# Oscillator.net
KiCad netlist of a schematic drawn in Altium Designer
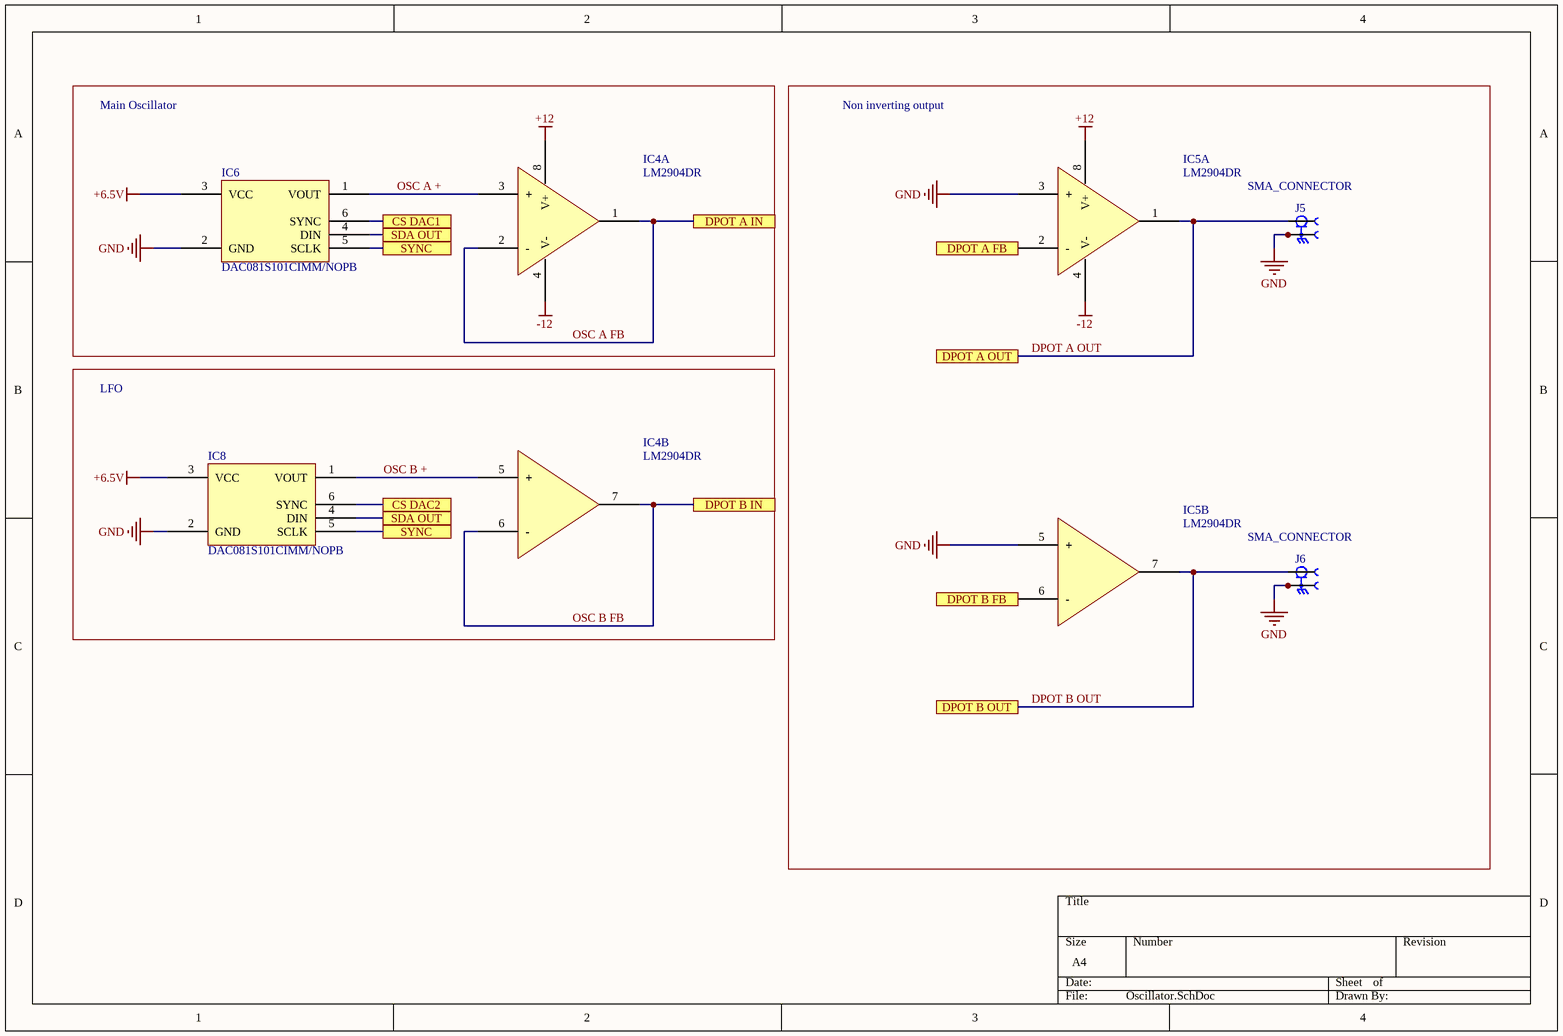
[diagram p0: Oscillator.SchDoc]

(export (version "E")
  (design (tool "Eeschema 10.0.6"))
  (components
    (comp (ref "IC4")
      (value "LM2904DR")
      (footprint "TI SOIC-8 D")
      (description "IC OPAMP GP 2 CIRCUIT 8SOIC")
      (fields (field (name "MANUFACTURER") "Texas Instruments"))
      (libsource (lib "Celestial Altium Library - altium_library(1)") (part "TI LM2904DR"))
    )
    (comp (ref "IC5")
      (value "LM2904DR")
      (footprint "TI SOIC-8 D")
      (description "IC OPAMP GP 2 CIRCUIT 8SOIC")
      (fields (field (name "MANUFACTURER") "Texas Instruments"))
      (libsource (lib "Celestial Altium Library - altium_library(1)") (part "TI LM2904DR"))
    )
    (comp (ref "IC6")
      (value "DAC081S101CIMM/NOPB")
      (footprint "TI VSSOP-8 DGK")
      (description "IC DAC 8BIT V-OUT 8VSSOP")
      (libsource (lib "Celestial Altium Library - altium_library(1)") (part "TI DAC081S101CIMM"))
    )
    (comp (ref "IC8")
      (value "DAC081S101CIMM/NOPB")
      (footprint "TI VSSOP-8 DGK")
      (description "IC DAC 8BIT V-OUT 8VSSOP")
      (libsource (lib "Celestial Altium Library - altium_library(1)") (part "TI DAC081S101CIMM"))
    )
    (comp (ref "J5")
      (value "SMA_CONNECTOR")
      (footprint "LPRS_SMA_CONNECTOR")
      (description "Straight SMA Connector")
      (fields (field (name "MP") "altium_native_batch"))
      (libsource (lib "SMA_CONNECTOR") (part "SMA_CONNECTOR"))
    )
    (comp (ref "J6")
      (value "SMA_CONNECTOR")
      (footprint "LPRS_SMA_CONNECTOR")
      (description "Straight SMA Connector")
      (fields (field (name "MP") "altium_native_batch"))
      (libsource (lib "SMA_CONNECTOR") (part "SMA_CONNECTOR"))
    )
  )
  (nets
    (net (code "1") (name "+6.5V") (class "Default")
      (node (ref "IC6") (pin "3") (pinfunction "VCC_3") (pintype "passive"))
      (node (ref "IC8") (pin "3") (pinfunction "VCC_3") (pintype "passive"))
    )
    (net (code "2") (name "+12") (class "Default")
      (node (ref "IC4") (pin "8") (pinfunction "V+_8") (pintype "passive"))
      (node (ref "IC5") (pin "8") (pinfunction "V+_8") (pintype "passive"))
    )
    (net (code "3") (name "-12") (class "Default")
      (node (ref "IC4") (pin "4") (pinfunction "V-_4") (pintype "passive"))
      (node (ref "IC5") (pin "4") (pinfunction "V-_4") (pintype "passive"))
    )
    (net (code "4") (name "/CS DAC1") (class "Default")
      (node (ref "IC6") (pin "6") (pinfunction "SYNC_6") (pintype "passive"))
    )
    (net (code "5") (name "/CS DAC2") (class "Default")
      (node (ref "IC8") (pin "6") (pinfunction "SYNC_6") (pintype "passive"))
    )
    (net (code "6") (name "/DPOT A FB") (class "Default")
      (node (ref "IC5") (pin "2") (pinfunction "-_2") (pintype "passive"))
    )
    (net (code "7") (name "/DPOT A OUT") (class "Default")
      (node (ref "IC5") (pin "1") (pinfunction "OUTA_1") (pintype "passive"))
      (node (ref "J5") (pin "1") (pinfunction "1_1") (pintype "passive"))
    )
    (net (code "8") (name "/DPOT B FB") (class "Default")
      (node (ref "IC5") (pin "6") (pinfunction "-_6") (pintype "passive"))
    )
    (net (code "9") (name "/DPOT B OUT") (class "Default")
      (node (ref "IC5") (pin "7") (pinfunction "OUTB_7") (pintype "passive"))
      (node (ref "J6") (pin "1") (pinfunction "1_1") (pintype "passive"))
    )
    (net (code "10") (name "/OSC A +") (class "Default")
      (node (ref "IC4") (pin "3") (pinfunction "+_3") (pintype "passive"))
      (node (ref "IC6") (pin "1") (pinfunction "VOUT_1") (pintype "passive"))
    )
    (net (code "11") (name "/OSC A FB") (class "Default")
      (node (ref "IC4") (pin "1") (pinfunction "OUTA_1") (pintype "passive"))
      (node (ref "IC4") (pin "2") (pinfunction "-_2") (pintype "passive"))
    )
    (net (code "12") (name "/OSC B +") (class "Default")
      (node (ref "IC4") (pin "5") (pinfunction "+_5") (pintype "passive"))
      (node (ref "IC8") (pin "1") (pinfunction "VOUT_1") (pintype "passive"))
    )
    (net (code "13") (name "/OSC B FB") (class "Default")
      (node (ref "IC4") (pin "6") (pinfunction "-_6") (pintype "passive"))
      (node (ref "IC4") (pin "7") (pinfunction "OUTB_7") (pintype "passive"))
    )
    (net (code "14") (name "/SDA OUT") (class "Default")
      (node (ref "IC6") (pin "4") (pinfunction "DIN_4") (pintype "passive"))
      (node (ref "IC8") (pin "4") (pinfunction "DIN_4") (pintype "passive"))
    )
    (net (code "15") (name "/SYNC") (class "Default")
      (node (ref "IC6") (pin "5") (pinfunction "SCLK_5") (pintype "passive"))
      (node (ref "IC8") (pin "5") (pinfunction "SCLK_5") (pintype "passive"))
    )
    (net (code "16") (name "GND") (class "Default")
      (node (ref "IC5") (pin "3") (pinfunction "+_3") (pintype "passive"))
      (node (ref "IC5") (pin "5") (pinfunction "+_5") (pintype "passive"))
      (node (ref "IC6") (pin "2") (pinfunction "GND_2") (pintype "passive"))
      (node (ref "IC8") (pin "2") (pinfunction "GND_2") (pintype "passive"))
      (node (ref "J5") (pin "G1") (pinfunction "2_G1") (pintype "passive"))
      (node (ref "J5") (pin "G2") (pinfunction "2_G2") (pintype "passive"))
      (node (ref "J5") (pin "G3") (pinfunction "2_G3") (pintype "passive"))
      (node (ref "J5") (pin "G4") (pinfunction "2_G4") (pintype "passive"))
      (node (ref "J6") (pin "G1") (pinfunction "2_G1") (pintype "passive"))
      (node (ref "J6") (pin "G2") (pinfunction "2_G2") (pintype "passive"))
      (node (ref "J6") (pin "G3") (pinfunction "2_G3") (pintype "passive"))
      (node (ref "J6") (pin "G4") (pinfunction "2_G4") (pintype "passive"))
    )
  )
)
